# DFPlayer-Wemos-GPIO_control.net
KiCad netlist of a schematic drawn in EAGLE
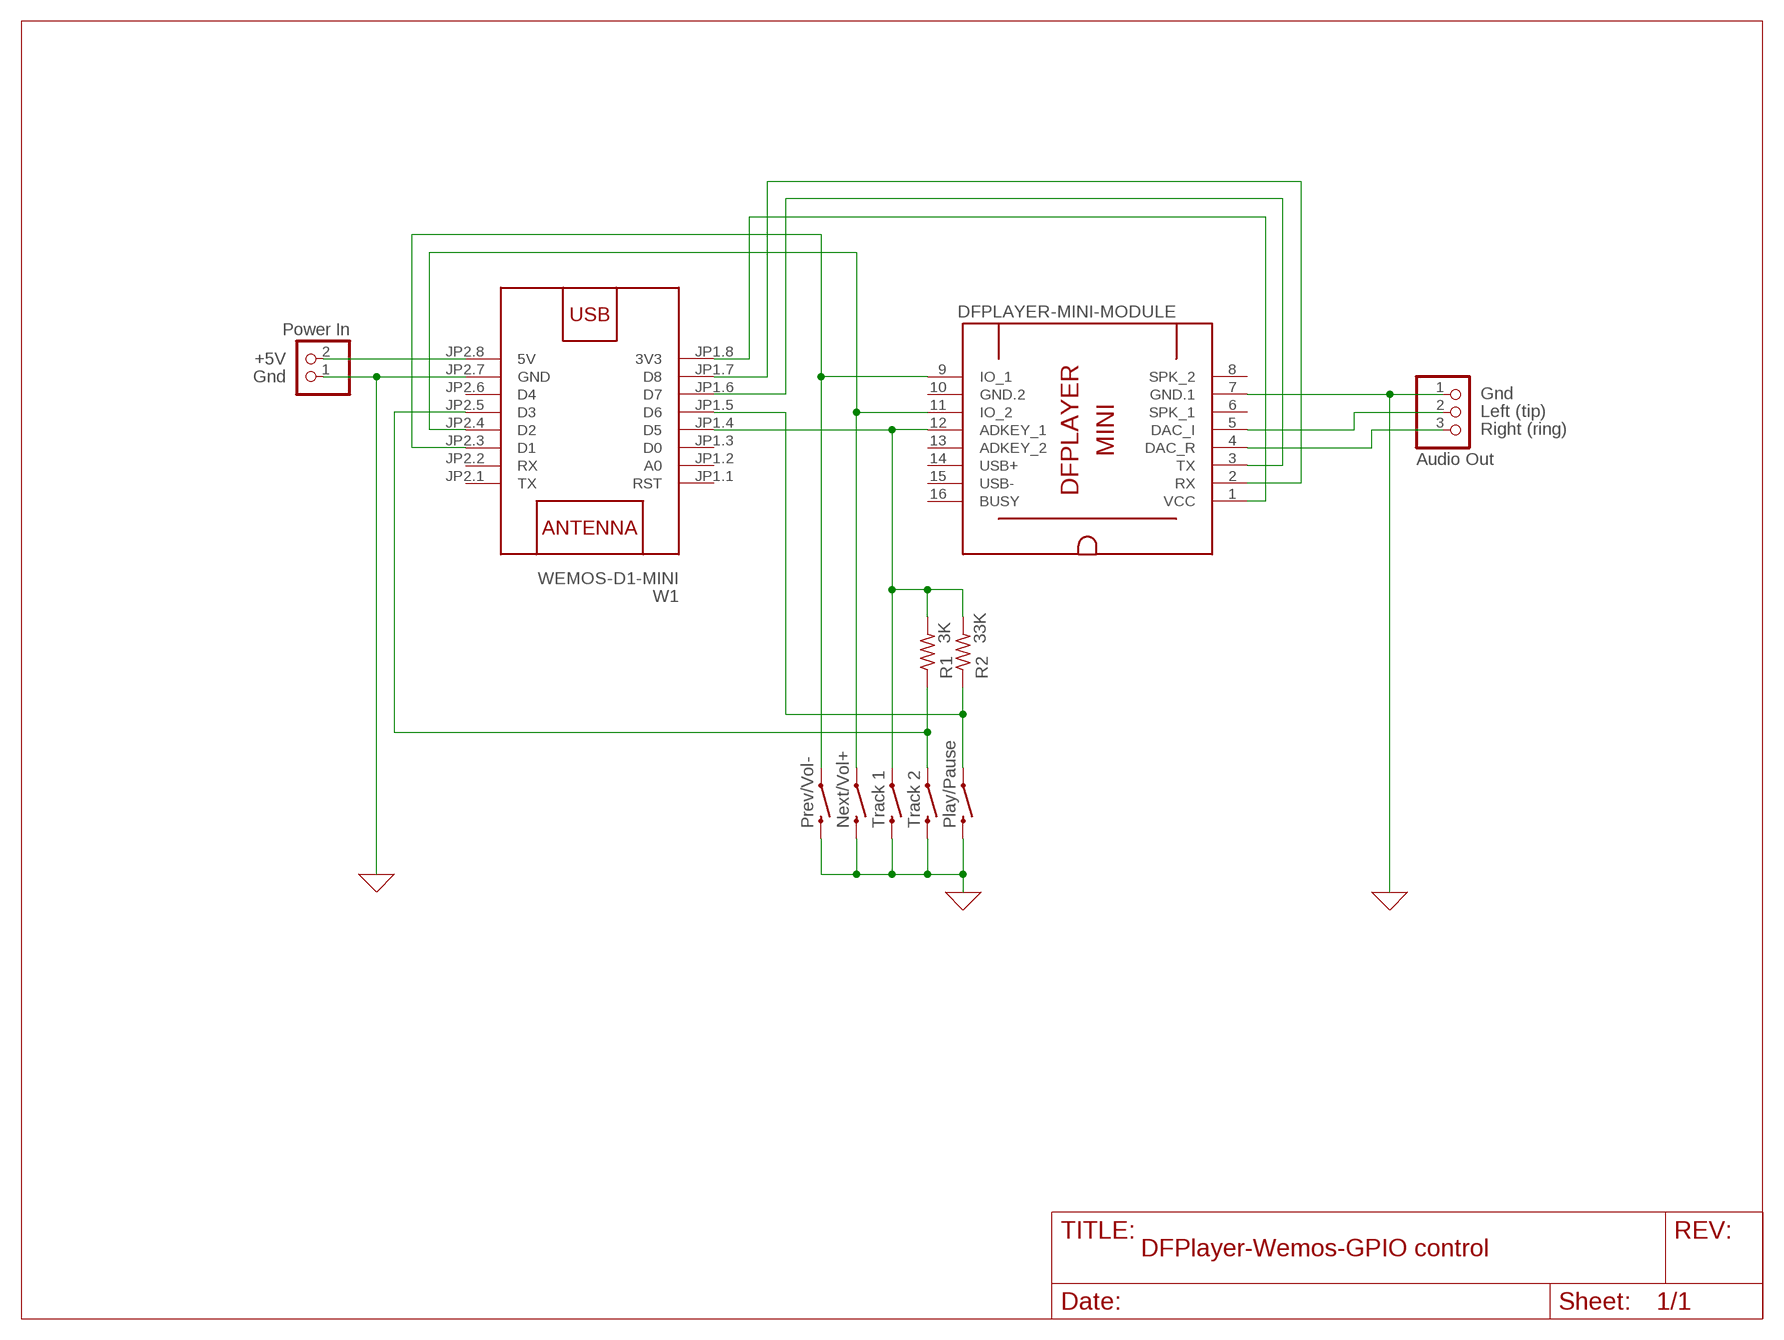
[diagram p0: schematic, sheet 1]

(export (version "E")
  (design (tool "Eeschema 10.0.6"))
  (components
    (comp (ref "JP2")
      (value "Audio Out")
      (footprint "eagle-import:1X03")
      (libsource (lib "eagle-import") (part "PINHD-1X3"))
    )
    (comp (ref "JP3")
      (value "Power In")
      (footprint "eagle-import:1X02")
      (libsource (lib "eagle-import") (part "PINHD-1X2"))
    )
    (comp (ref "R1")
      (value "3K")
      (footprint "eagle-import:0207_10")
      (libsource (lib "eagle-import") (part "R-US_0207/10"))
    )
    (comp (ref "R2")
      (value "33K")
      (footprint "eagle-import:0207_10")
      (libsource (lib "eagle-import") (part "R-US_0207/10"))
    )
    (comp (ref "S2")
      (value "MOMENTARY-SWITCH-SPST-PTH-6.0MM")
      (footprint "eagle-import:TACTILE_SWITCH_PTH_6.0MM")
      (libsource (lib "eagle-import") (part "MOMENTARY-SWITCH-SPST-PTH-6.0MM"))
    )
    (comp (ref "S3")
      (value "MOMENTARY-SWITCH-SPST-PTH-6.0MM")
      (footprint "eagle-import:TACTILE_SWITCH_PTH_6.0MM")
      (libsource (lib "eagle-import") (part "MOMENTARY-SWITCH-SPST-PTH-6.0MM"))
    )
    (comp (ref "S4")
      (value "MOMENTARY-SWITCH-SPST-PTH-6.0MM")
      (footprint "eagle-import:TACTILE_SWITCH_PTH_6.0MM")
      (libsource (lib "eagle-import") (part "MOMENTARY-SWITCH-SPST-PTH-6.0MM"))
    )
    (comp (ref "S5")
      (value "MOMENTARY-SWITCH-SPST-PTH-6.0MM")
      (footprint "eagle-import:TACTILE_SWITCH_PTH_6.0MM")
      (libsource (lib "eagle-import") (part "MOMENTARY-SWITCH-SPST-PTH-6.0MM"))
    )
    (comp (ref "S6")
      (value "MOMENTARY-SWITCH-SPST-PTH-6.0MM")
      (footprint "eagle-import:TACTILE_SWITCH_PTH_6.0MM")
      (libsource (lib "eagle-import") (part "MOMENTARY-SWITCH-SPST-PTH-6.0MM"))
    )
    (comp (ref "U$1")
      (value "DFPLAYER-MINI-MODULE")
      (footprint "eagle-import:DFPLAYER-MINI-MODULE")
      (libsource (lib "eagle-import") (part "DFPLAYER-MINI-MODULE"))
    )
    (comp (ref "W1")
      (value "WEMOS-D1-MINI")
      (footprint "eagle-import:WEMOS-D1-MINI")
      (libsource (lib "eagle-import") (part "WEMOS-D1-MINI"))
    )
  )
  (nets
    (net (code "1") (name "/GND.2") (class "Default")
      (node (ref "U$1") (pin "10") (pinfunction "GND.2_10") (pintype "power_in"))
    )
    (net (code "2") (name "GND") (class "Default")
      (node (ref "JP2") (pin "1") (pinfunction "1_1") (pintype "passive"))
      (node (ref "JP3") (pin "1") (pinfunction "1_1") (pintype "passive"))
      (node (ref "S2") (pin "3") (pinfunction "2_3") (pintype "passive"))
      (node (ref "S3") (pin "3") (pinfunction "2_3") (pintype "passive"))
      (node (ref "S4") (pin "3") (pinfunction "2_3") (pintype "passive"))
      (node (ref "S5") (pin "3") (pinfunction "2_3") (pintype "passive"))
      (node (ref "S6") (pin "3") (pinfunction "2_3") (pintype "passive"))
      (node (ref "U$1") (pin "7") (pinfunction "GND.1_7") (pintype "power_in"))
      (node (ref "W1") (pin "JP2.7") (pinfunction "GND_JP2.7") (pintype "power_in"))
    )
    (net (code "3") (name "Net-(U$1-ADKEY_1)") (class "Default")
      (node (ref "R1") (pin "2") (pinfunction "2_2") (pintype "passive"))
      (node (ref "R2") (pin "2") (pinfunction "2_2") (pintype "passive"))
      (node (ref "S4") (pin "1") (pinfunction "1_1") (pintype "passive"))
      (node (ref "U$1") (pin "12") (pinfunction "ADKEY_1_12") (pintype "bidirectional"))
      (node (ref "W1") (pin "JP1.4") (pinfunction "D5_JP1.4") (pintype "bidirectional"))
    )
    (net (code "4") (name "Net-(U$1-DAC_I)") (class "Default")
      (node (ref "JP2") (pin "2") (pinfunction "2_2") (pintype "passive"))
      (node (ref "U$1") (pin "5") (pinfunction "DAC_I_5") (pintype "bidirectional"))
    )
    (net (code "5") (name "Net-(U$1-DAC_R)") (class "Default")
      (node (ref "JP2") (pin "3") (pinfunction "3_3") (pintype "passive"))
      (node (ref "U$1") (pin "4") (pinfunction "DAC_R_4") (pintype "bidirectional"))
    )
    (net (code "6") (name "Net-(U$1-IO_1)") (class "Default")
      (node (ref "S3") (pin "1") (pinfunction "1_1") (pintype "passive"))
      (node (ref "U$1") (pin "9") (pinfunction "IO_1_9") (pintype "bidirectional"))
      (node (ref "W1") (pin "JP2.3") (pinfunction "D1_JP2.3") (pintype "bidirectional"))
    )
    (net (code "7") (name "Net-(U$1-IO_2)") (class "Default")
      (node (ref "S2") (pin "1") (pinfunction "1_1") (pintype "passive"))
      (node (ref "U$1") (pin "11") (pinfunction "IO_2_11") (pintype "bidirectional"))
      (node (ref "W1") (pin "JP2.4") (pinfunction "D2_JP2.4") (pintype "bidirectional"))
    )
    (net (code "8") (name "Net-(U$1-RX)") (class "Default")
      (node (ref "U$1") (pin "2") (pinfunction "RX_2") (pintype "bidirectional"))
      (node (ref "W1") (pin "JP1.7") (pinfunction "D8_JP1.7") (pintype "bidirectional"))
    )
    (net (code "9") (name "Net-(U$1-TX)") (class "Default")
      (node (ref "U$1") (pin "3") (pinfunction "TX_3") (pintype "bidirectional"))
      (node (ref "W1") (pin "JP1.6") (pinfunction "D7_JP1.6") (pintype "bidirectional"))
    )
    (net (code "10") (name "Net-(U$1-VCC)") (class "Default")
      (node (ref "U$1") (pin "1") (pinfunction "VCC_1") (pintype "power_in"))
      (node (ref "W1") (pin "JP1.8") (pinfunction "3V3_JP1.8") (pintype "power_in"))
    )
    (net (code "11") (name "Net-(W1-5V)") (class "Default")
      (node (ref "JP3") (pin "2") (pinfunction "2_2") (pintype "passive"))
      (node (ref "W1") (pin "JP2.8") (pinfunction "5V_JP2.8") (pintype "power_in"))
    )
    (net (code "12") (name "Net-(W1-D3)") (class "Default")
      (node (ref "R1") (pin "1") (pinfunction "1_1") (pintype "passive"))
      (node (ref "S6") (pin "1") (pinfunction "1_1") (pintype "passive"))
      (node (ref "W1") (pin "JP2.5") (pinfunction "D3_JP2.5") (pintype "bidirectional"))
    )
    (net (code "13") (name "Net-(W1-D6)") (class "Default")
      (node (ref "R2") (pin "1") (pinfunction "1_1") (pintype "passive"))
      (node (ref "S5") (pin "1") (pinfunction "1_1") (pintype "passive"))
      (node (ref "W1") (pin "JP1.5") (pinfunction "D6_JP1.5") (pintype "bidirectional"))
    )
    (net (code "14") (name "unconnected-(U$1-ADKEY_2-Pad13)") (class "Default")
      (node (ref "U$1") (pin "13") (pinfunction "ADKEY_2_13") (pintype "bidirectional"))
    )
    (net (code "15") (name "unconnected-(U$1-BUSY-Pad16)") (class "Default")
      (node (ref "U$1") (pin "16") (pinfunction "BUSY_16") (pintype "bidirectional"))
    )
    (net (code "16") (name "unconnected-(U$1-SPK_1-Pad6)") (class "Default")
      (node (ref "U$1") (pin "6") (pinfunction "SPK_1_6") (pintype "bidirectional"))
    )
    (net (code "17") (name "unconnected-(U$1-SPK_2-Pad8)") (class "Default")
      (node (ref "U$1") (pin "8") (pinfunction "SPK_2_8") (pintype "bidirectional"))
    )
    (net (code "18") (name "unconnected-(U$1-USB+-Pad14)") (class "Default")
      (node (ref "U$1") (pin "14") (pinfunction "USB+_14") (pintype "bidirectional"))
    )
    (net (code "19") (name "unconnected-(U$1-USB--Pad15)") (class "Default")
      (node (ref "U$1") (pin "15") (pinfunction "USB-_15") (pintype "bidirectional"))
    )
    (net (code "20") (name "unconnected-(W1-A0-PadJP1.2)") (class "Default")
      (node (ref "W1") (pin "JP1.2") (pinfunction "A0_JP1.2") (pintype "bidirectional"))
    )
    (net (code "21") (name "unconnected-(W1-D0-PadJP1.3)") (class "Default")
      (node (ref "W1") (pin "JP1.3") (pinfunction "D0_JP1.3") (pintype "bidirectional"))
    )
    (net (code "22") (name "unconnected-(W1-D4-PadJP2.6)") (class "Default")
      (node (ref "W1") (pin "JP2.6") (pinfunction "D4_JP2.6") (pintype "bidirectional"))
    )
    (net (code "23") (name "unconnected-(W1-RST-PadJP1.1)") (class "Default")
      (node (ref "W1") (pin "JP1.1") (pinfunction "RST_JP1.1") (pintype "bidirectional"))
    )
    (net (code "24") (name "unconnected-(W1-RX-PadJP2.2)") (class "Default")
      (node (ref "W1") (pin "JP2.2") (pinfunction "RX_JP2.2") (pintype "bidirectional"))
    )
    (net (code "25") (name "unconnected-(W1-TX-PadJP2.1)") (class "Default")
      (node (ref "W1") (pin "JP2.1") (pinfunction "TX_JP2.1") (pintype "bidirectional"))
    )
  )
)
